# infnoise.net
KiCad netlist of a schematic drawn in EAGLE
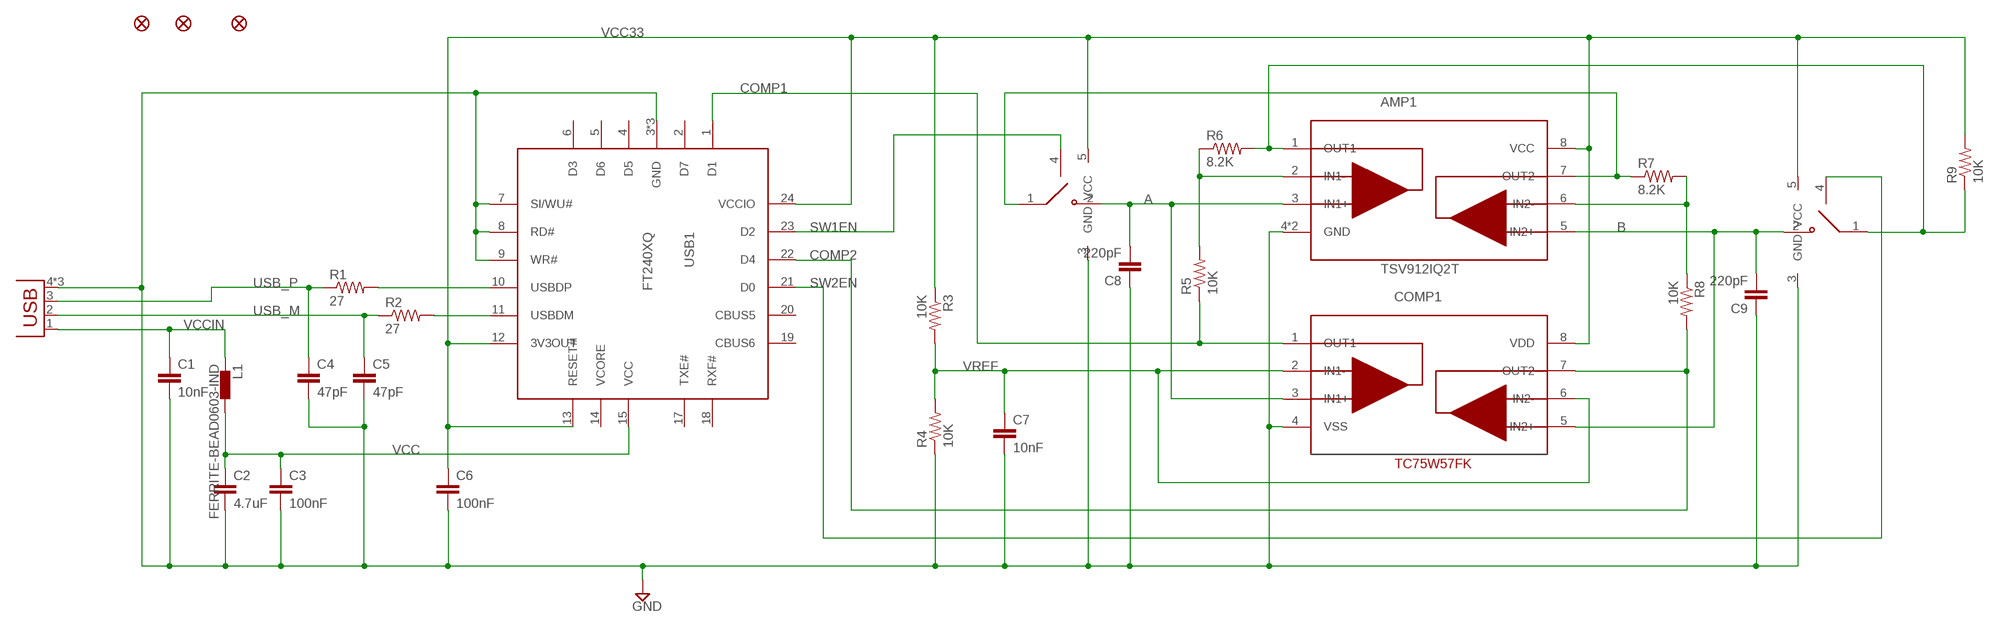
[diagram p0: schematic, sheet 1]

(export (version "E")
  (design (tool "Eeschema 10.0.6"))
  (components
    (comp (ref "AMP1")
      (value "TSV912IQ2T")
      (footprint "eagle-import:DFN8-2X3")
      (libsource (lib "eagle-import") (part "TSV912IQ2T"))
    )
    (comp (ref "C1")
      (value "10nF")
      (footprint "eagle-import:0603-CAP")
      (libsource (lib "eagle-import") (part "CAP0603-CAP"))
    )
    (comp (ref "C2")
      (value "4.7uF")
      (footprint "eagle-import:0603-CAP")
      (libsource (lib "eagle-import") (part "CAP0603-CAP"))
    )
    (comp (ref "C3")
      (value "100nF")
      (footprint "eagle-import:0603-CAP")
      (libsource (lib "eagle-import") (part "CAP0603-CAP"))
    )
    (comp (ref "C4")
      (value "47pF")
      (footprint "eagle-import:0603-CAP")
      (libsource (lib "eagle-import") (part "CAP0603-CAP"))
    )
    (comp (ref "C5")
      (value "47pF")
      (footprint "eagle-import:0603-CAP")
      (libsource (lib "eagle-import") (part "CAP0603-CAP"))
    )
    (comp (ref "C6")
      (value "100nF")
      (footprint "eagle-import:0603-CAP")
      (libsource (lib "eagle-import") (part "CAP0603-CAP"))
    )
    (comp (ref "C7")
      (value "10nF")
      (footprint "eagle-import:0603-CAP")
      (libsource (lib "eagle-import") (part "CAP0603-CAP"))
    )
    (comp (ref "C8")
      (value "220pF")
      (footprint "eagle-import:0603-CAP")
      (libsource (lib "eagle-import") (part "CAP0603-CAP"))
    )
    (comp (ref "C9")
      (value "220pF")
      (footprint "eagle-import:0603-CAP")
      (libsource (lib "eagle-import") (part "CAP0603-CAP"))
    )
    (comp (ref "COMP1")
      (value "TC75W57FK")
      (footprint "eagle-import:SSOP8-P-0.50A")
      (libsource (lib "eagle-import") (part "TC75W57FK"))
    )
    (comp (ref "FID1")
      (value "FIDUCIALUFIDUCIAL")
      (footprint "eagle-import:MICRO-FIDUCIAL")
      (libsource (lib "eagle-import") (part "FIDUCIALUFIDUCIAL"))
    )
    (comp (ref "FID2")
      (value "FIDUCIALUFIDUCIAL")
      (footprint "eagle-import:MICRO-FIDUCIAL")
      (libsource (lib "eagle-import") (part "FIDUCIALUFIDUCIAL"))
    )
    (comp (ref "FID3")
      (value "FIDUCIALUFIDUCIAL")
      (footprint "eagle-import:MICRO-FIDUCIAL")
      (libsource (lib "eagle-import") (part "FIDUCIALUFIDUCIAL"))
    )
    (comp (ref "L1")
      (value "FERRITE-BEAD0603-IND")
      (footprint "eagle-import:0603-IND")
      (libsource (lib "eagle-import") (part "FERRITE-BEAD0603-IND"))
    )
    (comp (ref "R1")
      (value "27")
      (footprint "eagle-import:0603-RES")
      (libsource (lib "eagle-import") (part "RESISTOR0603-RES"))
    )
    (comp (ref "R2")
      (value "27")
      (footprint "eagle-import:0603-RES")
      (libsource (lib "eagle-import") (part "RESISTOR0603-RES"))
    )
    (comp (ref "R3")
      (value "10K")
      (footprint "eagle-import:0603-RES")
      (libsource (lib "eagle-import") (part "RESISTOR0603-RES"))
    )
    (comp (ref "R4")
      (value "10K")
      (footprint "eagle-import:0603-RES")
      (libsource (lib "eagle-import") (part "RESISTOR0603-RES"))
    )
    (comp (ref "R5")
      (value "10K")
      (footprint "eagle-import:0603-RES")
      (libsource (lib "eagle-import") (part "RESISTOR0603-RES"))
    )
    (comp (ref "R6")
      (value "8.2K")
      (footprint "eagle-import:0603-RES")
      (libsource (lib "eagle-import") (part "RESISTOR0603-RES"))
    )
    (comp (ref "R7")
      (value "8.2K")
      (footprint "eagle-import:0603-RES")
      (libsource (lib "eagle-import") (part "RESISTOR0603-RES"))
    )
    (comp (ref "R8")
      (value "10K")
      (footprint "eagle-import:0603-RES")
      (libsource (lib "eagle-import") (part "RESISTOR0603-RES"))
    )
    (comp (ref "R9")
      (value "10K")
      (footprint "eagle-import:0603-RES")
      (libsource (lib "eagle-import") (part "RESISTOR0603-RES"))
    )
    (comp (ref "SW1")
      (value "MC74VHC1G66DFT1G")
      (footprint "eagle-import:SC70-5L")
      (libsource (lib "eagle-import") (part "MC74VHC1G66DFT1G"))
    )
    (comp (ref "SW2")
      (value "MC74VHC1G66DFT1G")
      (footprint "eagle-import:SC70-5L")
      (libsource (lib "eagle-import") (part "MC74VHC1G66DFT1G"))
    )
    (comp (ref "USB1")
      (value "FT240XQ")
      (footprint "eagle-import:QFN24-4X4")
      (libsource (lib "eagle-import") (part "FT240XQ"))
    )
    (comp (ref "X1")
      (value "USBSMT-MALE")
      (footprint "eagle-import:USB-A-SMT-MALE")
      (libsource (lib "eagle-import") (part "USBSMT-MALE"))
    )
  )
  (nets
    (net (code "1") (name "/A") (class "Default")
      (node (ref "AMP1") (pin "3") (pinfunction "IN1+_3") (pintype "bidirectional"))
      (node (ref "C8") (pin "2") (pinfunction "2_2") (pintype "passive"))
      (node (ref "COMP1") (pin "3") (pinfunction "IN1+_3") (pintype "bidirectional"))
      (node (ref "SW1") (pin "2") (pinfunction "NO_2") (pintype "bidirectional"))
    )
    (net (code "2") (name "/B") (class "Default")
      (node (ref "AMP1") (pin "5") (pinfunction "IN2+_5") (pintype "bidirectional"))
      (node (ref "C9") (pin "2") (pinfunction "2_2") (pintype "passive"))
      (node (ref "COMP1") (pin "5") (pinfunction "IN2+_5") (pintype "bidirectional"))
      (node (ref "SW2") (pin "2") (pinfunction "NO_2") (pintype "bidirectional"))
    )
    (net (code "3") (name "/COMP1") (class "Default")
      (node (ref "COMP1") (pin "1") (pinfunction "OUT1_1") (pintype "bidirectional"))
      (node (ref "R5") (pin "1") (pinfunction "1_1") (pintype "passive"))
      (node (ref "USB1") (pin "1") (pinfunction "D1_1") (pintype "bidirectional"))
    )
    (net (code "4") (name "/COMP2") (class "Default")
      (node (ref "COMP1") (pin "7") (pinfunction "OUT2_7") (pintype "bidirectional"))
      (node (ref "R8") (pin "2") (pinfunction "2_2") (pintype "passive"))
      (node (ref "USB1") (pin "22") (pinfunction "D4_22") (pintype "bidirectional"))
    )
    (net (code "5") (name "/SW1EN") (class "Default")
      (node (ref "SW1") (pin "4") (pinfunction "IN_4") (pintype "bidirectional"))
      (node (ref "USB1") (pin "23") (pinfunction "D2_23") (pintype "bidirectional"))
    )
    (net (code "6") (name "/SW2EN") (class "Default")
      (node (ref "SW2") (pin "4") (pinfunction "IN_4") (pintype "bidirectional"))
      (node (ref "USB1") (pin "21") (pinfunction "D0_21") (pintype "bidirectional"))
    )
    (net (code "7") (name "/USB_M") (class "Default")
      (node (ref "C5") (pin "1") (pinfunction "1_1") (pintype "passive"))
      (node (ref "R2") (pin "1") (pinfunction "1_1") (pintype "passive"))
      (node (ref "X1") (pin "2") (pinfunction "D-_2") (pintype "bidirectional"))
    )
    (net (code "8") (name "/USB_P") (class "Default")
      (node (ref "C4") (pin "1") (pinfunction "1_1") (pintype "passive"))
      (node (ref "R1") (pin "1") (pinfunction "1_1") (pintype "passive"))
      (node (ref "X1") (pin "3") (pinfunction "D+_3") (pintype "bidirectional"))
    )
    (net (code "9") (name "/VCC") (class "Default")
      (node (ref "C2") (pin "1") (pinfunction "1_1") (pintype "passive"))
      (node (ref "C3") (pin "1") (pinfunction "1_1") (pintype "passive"))
      (node (ref "L1") (pin "2") (pinfunction "2_2") (pintype "passive"))
      (node (ref "USB1") (pin "15") (pinfunction "VCC_15") (pintype "bidirectional"))
    )
    (net (code "10") (name "/VCC33") (class "Default")
      (node (ref "AMP1") (pin "8") (pinfunction "VCC_8") (pintype "bidirectional"))
      (node (ref "C6") (pin "1") (pinfunction "1_1") (pintype "passive"))
      (node (ref "COMP1") (pin "8") (pinfunction "VDD_8") (pintype "bidirectional"))
      (node (ref "R3") (pin "1") (pinfunction "1_1") (pintype "passive"))
      (node (ref "R9") (pin "2") (pinfunction "2_2") (pintype "passive"))
      (node (ref "SW1") (pin "5") (pinfunction "VCC_5") (pintype "bidirectional"))
      (node (ref "SW2") (pin "5") (pinfunction "VCC_5") (pintype "bidirectional"))
      (node (ref "USB1") (pin "12") (pinfunction "3V3OUT_12") (pintype "bidirectional"))
      (node (ref "USB1") (pin "13") (pinfunction "RESET#_13") (pintype "bidirectional"))
      (node (ref "USB1") (pin "24") (pinfunction "VCCIO_24") (pintype "bidirectional"))
    )
    (net (code "11") (name "/VCCIN") (class "Default")
      (node (ref "C1") (pin "1") (pinfunction "1_1") (pintype "passive"))
      (node (ref "L1") (pin "1") (pinfunction "1_1") (pintype "passive"))
      (node (ref "X1") (pin "1") (pinfunction "VCC_1") (pintype "bidirectional"))
    )
    (net (code "12") (name "/VREF") (class "Default")
      (node (ref "C7") (pin "1") (pinfunction "1_1") (pintype "passive"))
      (node (ref "COMP1") (pin "2") (pinfunction "IN1-_2") (pintype "bidirectional"))
      (node (ref "COMP1") (pin "6") (pinfunction "IN2-_6") (pintype "bidirectional"))
      (node (ref "R3") (pin "2") (pinfunction "2_2") (pintype "passive"))
      (node (ref "R4") (pin "2") (pinfunction "2_2") (pintype "passive"))
    )
    (net (code "13") (name "GND") (class "Default")
      (node (ref "AMP1") (pin "4") (pinfunction "GND_4") (pintype "bidirectional"))
      (node (ref "AMP1") (pin "EXP") (pinfunction "GND_EXP") (pintype "bidirectional"))
      (node (ref "C1") (pin "2") (pinfunction "2_2") (pintype "passive"))
      (node (ref "C2") (pin "2") (pinfunction "2_2") (pintype "passive"))
      (node (ref "C3") (pin "2") (pinfunction "2_2") (pintype "passive"))
      (node (ref "C4") (pin "2") (pinfunction "2_2") (pintype "passive"))
      (node (ref "C5") (pin "2") (pinfunction "2_2") (pintype "passive"))
      (node (ref "C6") (pin "2") (pinfunction "2_2") (pintype "passive"))
      (node (ref "C7") (pin "2") (pinfunction "2_2") (pintype "passive"))
      (node (ref "C8") (pin "1") (pinfunction "1_1") (pintype "passive"))
      (node (ref "C9") (pin "1") (pinfunction "1_1") (pintype "passive"))
      (node (ref "COMP1") (pin "4") (pinfunction "VSS_4") (pintype "bidirectional"))
      (node (ref "R4") (pin "1") (pinfunction "1_1") (pintype "passive"))
      (node (ref "SW1") (pin "3") (pinfunction "GND_3") (pintype "bidirectional"))
      (node (ref "SW2") (pin "3") (pinfunction "GND_3") (pintype "bidirectional"))
      (node (ref "USB1") (pin "16") (pinfunction "GND_16") (pintype "bidirectional"))
      (node (ref "USB1") (pin "3") (pinfunction "GND_3") (pintype "bidirectional"))
      (node (ref "USB1") (pin "7") (pinfunction "SI/WU#_7") (pintype "bidirectional"))
      (node (ref "USB1") (pin "8") (pinfunction "RD#_8") (pintype "bidirectional"))
      (node (ref "USB1") (pin "9") (pinfunction "WR#_9") (pintype "bidirectional"))
      (node (ref "USB1") (pin "EXP") (pinfunction "GND_EXP") (pintype "bidirectional"))
      (node (ref "X1") (pin "4") (pinfunction "GND_4") (pintype "bidirectional"))
      (node (ref "X1") (pin "P$1") (pinfunction "GND_P$1") (pintype "bidirectional"))
      (node (ref "X1") (pin "P$3") (pinfunction "GND_P$3") (pintype "bidirectional"))
    )
    (net (code "14") (name "Net-(AMP1-IN1-)") (class "Default")
      (node (ref "AMP1") (pin "2") (pinfunction "IN1-_2") (pintype "bidirectional"))
      (node (ref "R5") (pin "2") (pinfunction "2_2") (pintype "passive"))
      (node (ref "R6") (pin "1") (pinfunction "1_1") (pintype "passive"))
    )
    (net (code "15") (name "Net-(AMP1-IN2-)") (class "Default")
      (node (ref "AMP1") (pin "6") (pinfunction "IN2-_6") (pintype "bidirectional"))
      (node (ref "R7") (pin "2") (pinfunction "2_2") (pintype "passive"))
      (node (ref "R8") (pin "1") (pinfunction "1_1") (pintype "passive"))
    )
    (net (code "16") (name "Net-(AMP1-OUT1)") (class "Default")
      (node (ref "AMP1") (pin "1") (pinfunction "OUT1_1") (pintype "bidirectional"))
      (node (ref "R6") (pin "2") (pinfunction "2_2") (pintype "passive"))
      (node (ref "R9") (pin "1") (pinfunction "1_1") (pintype "passive"))
      (node (ref "SW2") (pin "1") (pinfunction "COM_1") (pintype "bidirectional"))
    )
    (net (code "17") (name "Net-(AMP1-OUT2)") (class "Default")
      (node (ref "AMP1") (pin "7") (pinfunction "OUT2_7") (pintype "bidirectional"))
      (node (ref "R7") (pin "1") (pinfunction "1_1") (pintype "passive"))
      (node (ref "SW1") (pin "1") (pinfunction "COM_1") (pintype "bidirectional"))
    )
    (net (code "18") (name "Net-(USB1-USBDM)") (class "Default")
      (node (ref "R2") (pin "2") (pinfunction "2_2") (pintype "passive"))
      (node (ref "USB1") (pin "11") (pinfunction "USBDM_11") (pintype "bidirectional"))
    )
    (net (code "19") (name "Net-(USB1-USBDP)") (class "Default")
      (node (ref "R1") (pin "2") (pinfunction "2_2") (pintype "passive"))
      (node (ref "USB1") (pin "10") (pinfunction "USBDP_10") (pintype "bidirectional"))
    )
    (net (code "20") (name "unconnected-(USB1-CBUS5-Pad20)") (class "Default")
      (node (ref "USB1") (pin "20") (pinfunction "CBUS5_20") (pintype "bidirectional"))
    )
    (net (code "21") (name "unconnected-(USB1-CBUS6-Pad19)") (class "Default")
      (node (ref "USB1") (pin "19") (pinfunction "CBUS6_19") (pintype "bidirectional"))
    )
    (net (code "22") (name "unconnected-(USB1-D3-Pad6)") (class "Default")
      (node (ref "USB1") (pin "6") (pinfunction "D3_6") (pintype "bidirectional"))
    )
    (net (code "23") (name "unconnected-(USB1-D5-Pad4)") (class "Default")
      (node (ref "USB1") (pin "4") (pinfunction "D5_4") (pintype "bidirectional"))
    )
    (net (code "24") (name "unconnected-(USB1-D6-Pad5)") (class "Default")
      (node (ref "USB1") (pin "5") (pinfunction "D6_5") (pintype "bidirectional"))
    )
    (net (code "25") (name "unconnected-(USB1-D7-Pad2)") (class "Default")
      (node (ref "USB1") (pin "2") (pinfunction "D7_2") (pintype "bidirectional"))
    )
    (net (code "26") (name "unconnected-(USB1-RXF#-Pad18)") (class "Default")
      (node (ref "USB1") (pin "18") (pinfunction "RXF#_18") (pintype "bidirectional"))
    )
    (net (code "27") (name "unconnected-(USB1-TXE#-Pad17)") (class "Default")
      (node (ref "USB1") (pin "17") (pinfunction "TXE#_17") (pintype "bidirectional"))
    )
    (net (code "28") (name "unconnected-(USB1-VCORE-Pad14)") (class "Default")
      (node (ref "USB1") (pin "14") (pinfunction "VCORE_14") (pintype "bidirectional"))
    )
  )
)
